# 05_RS485.net
KiCad netlist of a schematic drawn in Altium Designer
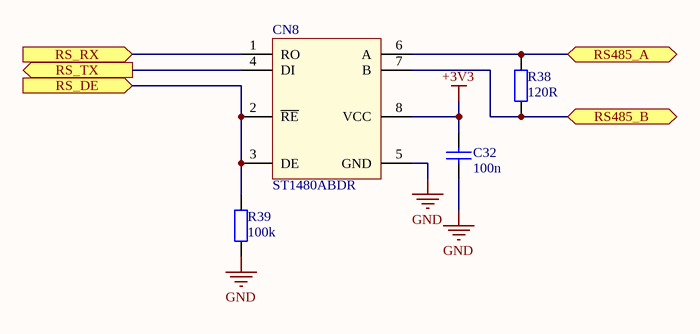
[diagram p0: 05_RS485.SchDoc]

(export (version "E")
  (design (tool "Eeschema 10.0.6"))
  (components
    (comp (ref "C32")
      (value "100n")
      (footprint "C0603_IPC_MD")
      (description "CAP CER 0.1UF 16V X7R 0603")
      (fields
        (field (name "MANUFACTURER") "Samsung Electro-Mechanics")
        (field (name "MANUFACTURER PART NUMBER") "CL10B104KO8WPNC")
      )
      (libsource (lib "alfasat_lib") (part "CL10B104KO8WPNC"))
    )
    (comp (ref "CN8")
      (value "ST1480ABDR")
      (footprint "SOIC-8")
      (description "IC TXRX 3.3V RS485/422 8 SOIC")
      (fields (field (name "MANUFACTURER") "STMicroelectronics"))
      (libsource (lib "alfasat_lib") (part "ST1480ABDR"))
    )
    (comp (ref "R38")
      (value "120R")
      (footprint "R0603_IPC_MD")
      (description "RES SMD 120 OHM 5% 1/10W 0603")
      (fields
        (field (name "MANUFACTURER") "Yageo")
        (field (name "MANUFACTURER PART NUMBER") "RC0603JR-07120RL")
      )
      (libsource (lib "alfasat_lib") (part "RC0603JR-07120RL"))
    )
    (comp (ref "R39")
      (value "100k")
      (footprint "R0603_IPC_MD")
      (description "RES 100K OHM 1% 1/10W 0603")
      (fields
        (field (name "MANUFACTURER") "Bourns Inc.")
        (field (name "MANUFACTURER PART NUMBER") "RMCF0603FT100K")
      )
      (libsource (lib "alfasat_lib") (part "RMCF0603FT100K"))
    )
  )
  (nets
    (net (code "1") (name "+3V3") (class "Default")
      (node (ref "C32") (pin "2") (pinfunction "2_2") (pintype "passive"))
      (node (ref "CN8") (pin "8") (pinfunction "VCC_8") (pintype "passive"))
    )
    (net (code "2") (name "/RS485_A") (class "Default")
      (node (ref "CN8") (pin "6") (pinfunction "A_6") (pintype "passive"))
      (node (ref "R38") (pin "2") (pinfunction "2_2") (pintype "passive"))
    )
    (net (code "3") (name "/RS485_B") (class "Default")
      (node (ref "CN8") (pin "7") (pinfunction "B_7") (pintype "passive"))
      (node (ref "R38") (pin "1") (pinfunction "1_1") (pintype "passive"))
    )
    (net (code "4") (name "/RS_DE") (class "Default")
      (node (ref "CN8") (pin "2") (pinfunction "~{RE}_2") (pintype "passive"))
      (node (ref "CN8") (pin "3") (pinfunction "DE_3") (pintype "passive"))
      (node (ref "R39") (pin "2") (pinfunction "2_2") (pintype "passive"))
    )
    (net (code "5") (name "/RS_RX") (class "Default")
      (node (ref "CN8") (pin "1") (pinfunction "RO_1") (pintype "passive"))
    )
    (net (code "6") (name "/RS_TX") (class "Default")
      (node (ref "CN8") (pin "4") (pinfunction "DI_4") (pintype "passive"))
    )
    (net (code "7") (name "GND") (class "Default")
      (node (ref "C32") (pin "1") (pinfunction "1_1") (pintype "passive"))
      (node (ref "CN8") (pin "5") (pinfunction "GND_5") (pintype "passive"))
      (node (ref "R39") (pin "1") (pinfunction "1_1") (pintype "passive"))
    )
  )
)
